# M710B.net
KiCad netlist of a schematic drawn in EAGLE
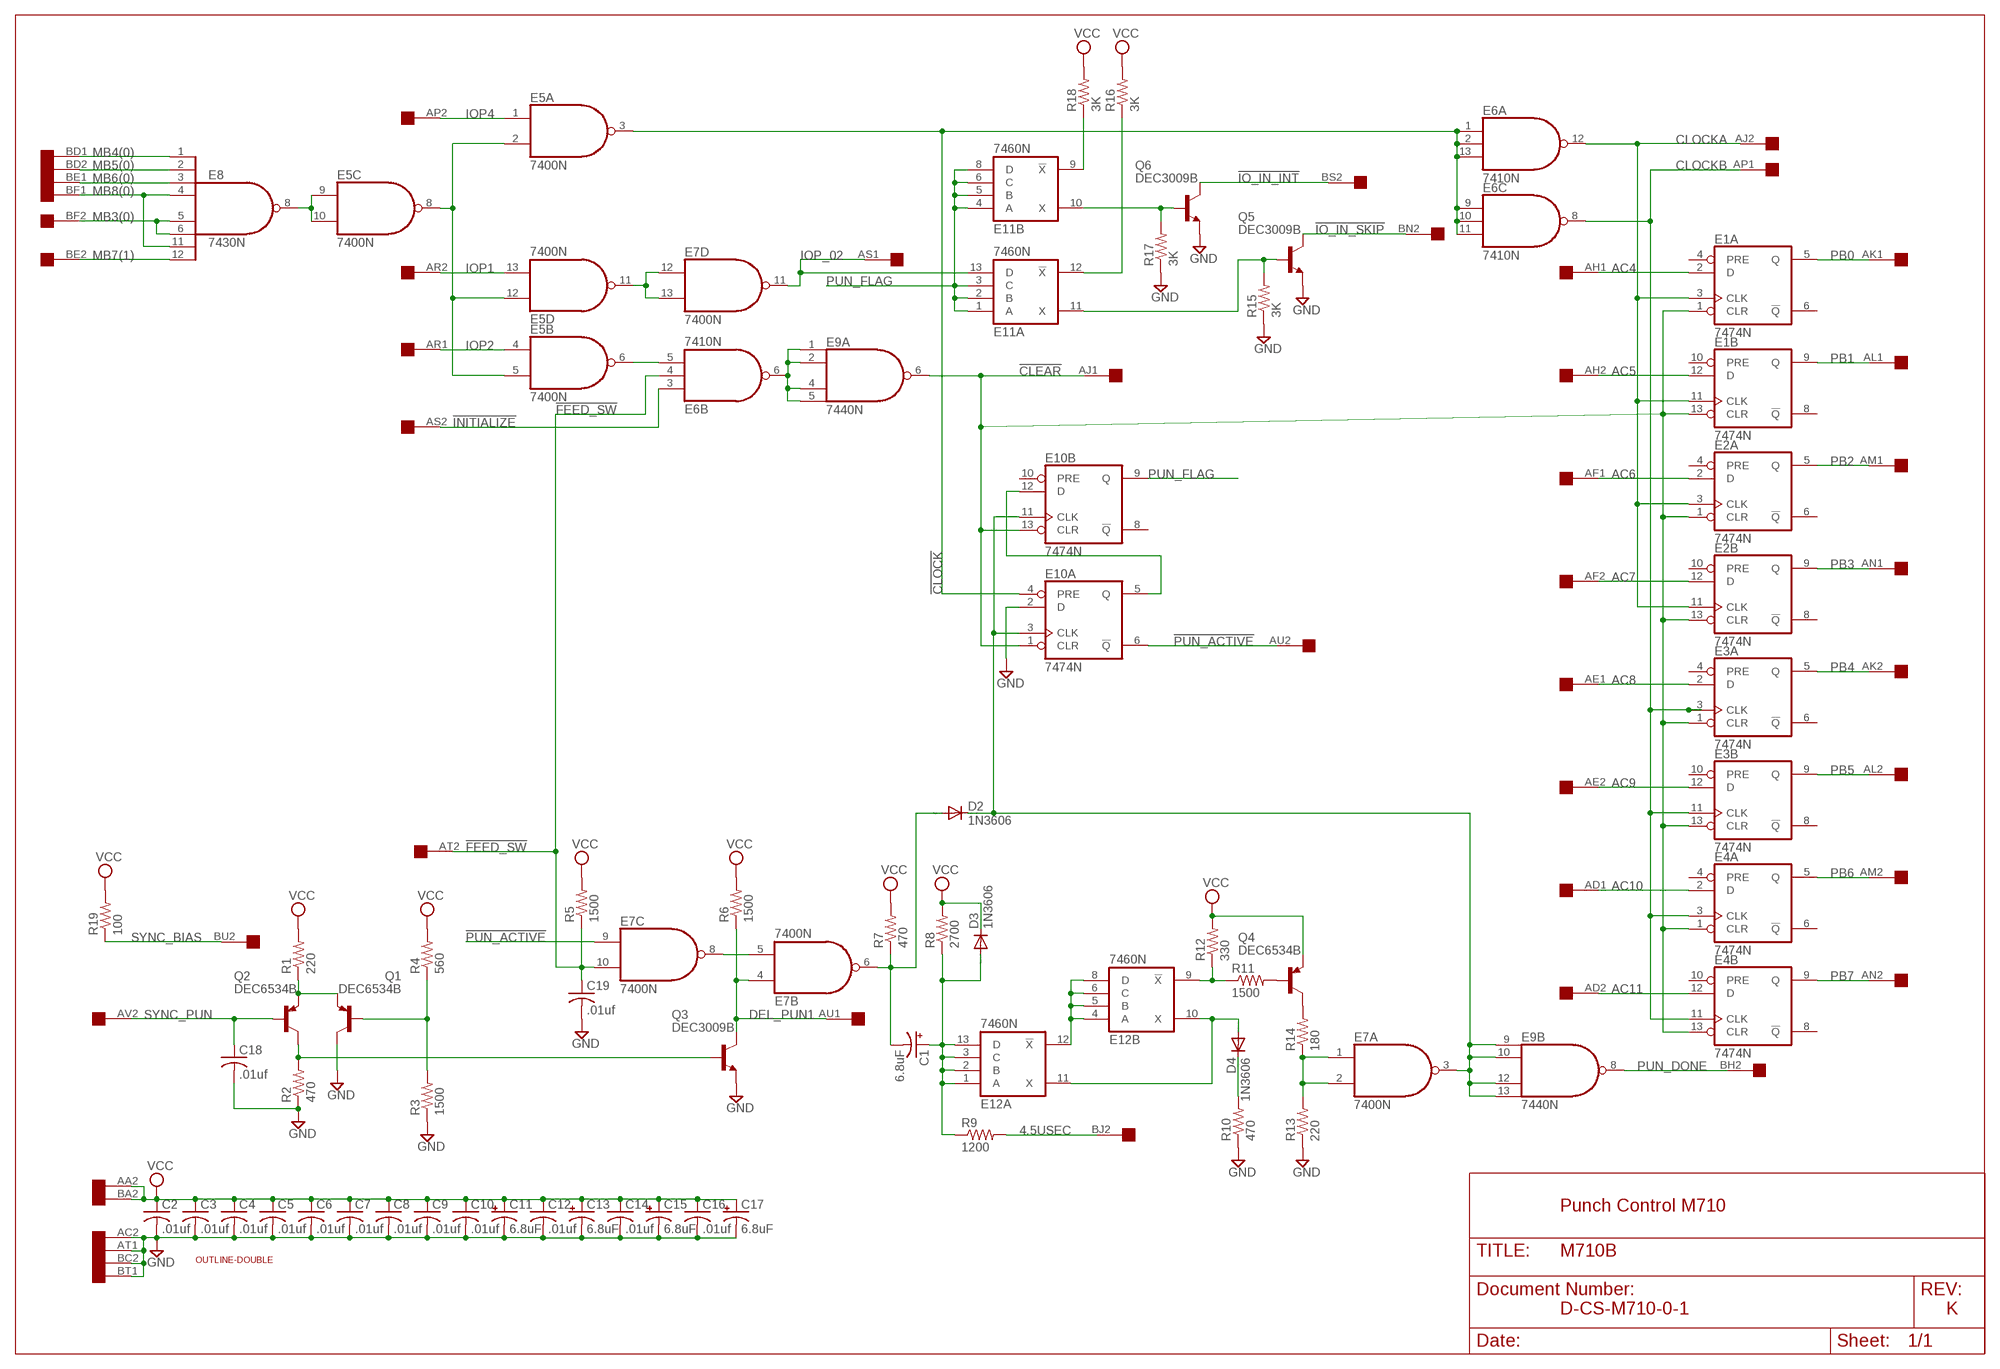
[diagram p0: schematic, sheet 1]

(export (version "E")
  (design (tool "Eeschema 10.0.6"))
  (components
    (comp (ref "C1")
      (value "6.8uF")
      (footprint "eagle-import:E15-5")
      (libsource (lib "eagle-import") (part "CPOL-USE15-5AXIAL"))
    )
    (comp (ref "C2")
      (value ".01uf")
      (footprint "eagle-import:C075-032X103")
      (libsource (lib "eagle-import") (part "C-US075-032X103"))
    )
    (comp (ref "C3")
      (value ".01uf")
      (footprint "eagle-import:C075-032X103")
      (libsource (lib "eagle-import") (part "C-US075-032X103"))
    )
    (comp (ref "C4")
      (value ".01uf")
      (footprint "eagle-import:C075-032X103")
      (libsource (lib "eagle-import") (part "C-US075-032X103"))
    )
    (comp (ref "C5")
      (value ".01uf")
      (footprint "eagle-import:C075-032X103")
      (libsource (lib "eagle-import") (part "C-US075-032X103"))
    )
    (comp (ref "C6")
      (value ".01uf")
      (footprint "eagle-import:C075-032X103")
      (libsource (lib "eagle-import") (part "C-US075-032X103"))
    )
    (comp (ref "C7")
      (value ".01uf")
      (footprint "eagle-import:C075-032X103")
      (libsource (lib "eagle-import") (part "C-US075-032X103"))
    )
    (comp (ref "C8")
      (value ".01uf")
      (footprint "eagle-import:C075-032X103")
      (libsource (lib "eagle-import") (part "C-US075-032X103"))
    )
    (comp (ref "C9")
      (value ".01uf")
      (footprint "eagle-import:C075-032X103")
      (libsource (lib "eagle-import") (part "C-US075-032X103"))
    )
    (comp (ref "C10")
      (value ".01uf")
      (footprint "eagle-import:C075-032X103")
      (libsource (lib "eagle-import") (part "C-US075-032X103"))
    )
    (comp (ref "C11")
      (value "6.8uF")
      (footprint "eagle-import:E15-5")
      (libsource (lib "eagle-import") (part "CPOL-USE15-5AXIAL"))
    )
    (comp (ref "C12")
      (value ".01uf")
      (footprint "eagle-import:C075-032X103")
      (libsource (lib "eagle-import") (part "C-US075-032X103"))
    )
    (comp (ref "C13")
      (value "6.8uF")
      (footprint "eagle-import:E15-5")
      (libsource (lib "eagle-import") (part "CPOL-USE15-5AXIAL"))
    )
    (comp (ref "C14")
      (value ".01uf")
      (footprint "eagle-import:C075-032X103")
      (libsource (lib "eagle-import") (part "C-US075-032X103"))
    )
    (comp (ref "C15")
      (value "6.8uF")
      (footprint "eagle-import:E15-5")
      (libsource (lib "eagle-import") (part "CPOL-USE15-5AXIAL"))
    )
    (comp (ref "C16")
      (value ".01uf")
      (footprint "eagle-import:C075-032X103")
      (libsource (lib "eagle-import") (part "C-US075-032X103"))
    )
    (comp (ref "C17")
      (value "6.8uF")
      (footprint "eagle-import:E15-5")
      (libsource (lib "eagle-import") (part "CPOL-USE15-5AXIAL"))
    )
    (comp (ref "C18")
      (value ".01uf")
      (footprint "eagle-import:C075-032X103")
      (libsource (lib "eagle-import") (part "C-US075-032X103"))
    )
    (comp (ref "C19")
      (value ".01uf")
      (footprint "eagle-import:C075-032X103")
      (libsource (lib "eagle-import") (part "C-US075-032X103"))
    )
    (comp (ref "D2")
      (value "1N3606")
      (footprint "eagle-import:SOD61B")
      (libsource (lib "eagle-import") (part "DIODE-SOD61B"))
    )
    (comp (ref "D3")
      (value "1N3606")
      (footprint "eagle-import:SOD61B")
      (libsource (lib "eagle-import") (part "DIODE-SOD61B"))
    )
    (comp (ref "D4")
      (value "1N3606")
      (footprint "eagle-import:SOD61B")
      (libsource (lib "eagle-import") (part "DIODE-SOD61B"))
    )
    (comp (ref "E1")
      (value "7474N")
      (footprint "eagle-import:DIL14")
      (libsource (lib "eagle-import") (part "7474NS"))
    )
    (comp (ref "E2")
      (value "7474N")
      (footprint "eagle-import:DIL14")
      (libsource (lib "eagle-import") (part "7474NS"))
    )
    (comp (ref "E3")
      (value "7474N")
      (footprint "eagle-import:DIL14")
      (libsource (lib "eagle-import") (part "7474NS"))
    )
    (comp (ref "E4")
      (value "7474N")
      (footprint "eagle-import:DIL14")
      (libsource (lib "eagle-import") (part "7474NS"))
    )
    (comp (ref "E5")
      (value "7400N")
      (footprint "eagle-import:DIL14")
      (libsource (lib "eagle-import") (part "7400N"))
    )
    (comp (ref "E6")
      (value "7410N")
      (footprint "eagle-import:DIL14")
      (libsource (lib "eagle-import") (part "7410N"))
    )
    (comp (ref "E7")
      (value "7400N")
      (footprint "eagle-import:DIL14")
      (libsource (lib "eagle-import") (part "7400N"))
    )
    (comp (ref "E8")
      (value "7430N")
      (footprint "eagle-import:DIL14")
      (libsource (lib "eagle-import") (part "7430N"))
    )
    (comp (ref "E9")
      (value "7440N")
      (footprint "eagle-import:DIL14")
      (libsource (lib "eagle-import") (part "7440N"))
    )
    (comp (ref "E10")
      (value "7474N")
      (footprint "eagle-import:DIL14")
      (libsource (lib "eagle-import") (part "7474NS"))
    )
    (comp (ref "E11")
      (value "7460N")
      (footprint "eagle-import:DIL14")
      (libsource (lib "eagle-import") (part "7460N"))
    )
    (comp (ref "E12")
      (value "7460N")
      (footprint "eagle-import:DIL14")
      (libsource (lib "eagle-import") (part "7460N"))
    )
    (comp (ref "Q1")
      (value "DEC6534B")
      (footprint "eagle-import:TO92-EBC")
      (libsource (lib "eagle-import") (part "-PNP-TO92-EBCBC327-16"))
    )
    (comp (ref "Q2")
      (value "DEC6534B")
      (footprint "eagle-import:TO92-EBC")
      (libsource (lib "eagle-import") (part "-PNP-TO92-EBCBC327-16"))
    )
    (comp (ref "Q3")
      (value "DEC3009B")
      (footprint "eagle-import:TO92-EBC")
      (libsource (lib "eagle-import") (part "-NPN-TO92-EBC92"))
    )
    (comp (ref "Q4")
      (value "DEC6534B")
      (footprint "eagle-import:TO92-EBC")
      (libsource (lib "eagle-import") (part "-PNP-TO92-EBCBC327-16"))
    )
    (comp (ref "Q5")
      (value "DEC3009B")
      (footprint "eagle-import:TO92-EBC")
      (libsource (lib "eagle-import") (part "-NPN-TO92-EBC92"))
    )
    (comp (ref "Q6")
      (value "DEC3009B")
      (footprint "eagle-import:TO92-EBC")
      (libsource (lib "eagle-import") (part "-NPN-TO92-EBC"))
    )
    (comp (ref "R1")
      (value "220")
      (footprint "eagle-import:0207_15")
      (libsource (lib "eagle-import") (part "R-US_0207/15"))
    )
    (comp (ref "R2")
      (value "470")
      (footprint "eagle-import:0207_15")
      (libsource (lib "eagle-import") (part "R-US_0207/15"))
    )
    (comp (ref "R3")
      (value "1500")
      (footprint "eagle-import:0207_15")
      (libsource (lib "eagle-import") (part "R-US_0207/15"))
    )
    (comp (ref "R4")
      (value "560")
      (footprint "eagle-import:0207_15")
      (libsource (lib "eagle-import") (part "R-US_0207/15"))
    )
    (comp (ref "R5")
      (value "1500")
      (footprint "eagle-import:0207_15")
      (libsource (lib "eagle-import") (part "R-US_0207/15"))
    )
    (comp (ref "R6")
      (value "1500")
      (footprint "eagle-import:0207_15")
      (libsource (lib "eagle-import") (part "R-US_0207/15"))
    )
    (comp (ref "R7")
      (value "470")
      (footprint "eagle-import:0207_15")
      (libsource (lib "eagle-import") (part "R-US_0207/15"))
    )
    (comp (ref "R8")
      (value "2700")
      (footprint "eagle-import:0207_15")
      (libsource (lib "eagle-import") (part "R-US_0207/15"))
    )
    (comp (ref "R9")
      (value "1200")
      (footprint "eagle-import:0207_15")
      (libsource (lib "eagle-import") (part "R-US_0207/15"))
    )
    (comp (ref "R10")
      (value "470")
      (footprint "eagle-import:0207_15")
      (libsource (lib "eagle-import") (part "R-US_0207/15"))
    )
    (comp (ref "R11")
      (value "1500")
      (footprint "eagle-import:0207_15")
      (libsource (lib "eagle-import") (part "R-US_0207/15"))
    )
    (comp (ref "R12")
      (value "330")
      (footprint "eagle-import:0207_15")
      (libsource (lib "eagle-import") (part "R-US_0207/15"))
    )
    (comp (ref "R13")
      (value "220")
      (footprint "eagle-import:0207_15")
      (libsource (lib "eagle-import") (part "R-US_0207/15"))
    )
    (comp (ref "R14")
      (value "180")
      (footprint "eagle-import:0207_15")
      (libsource (lib "eagle-import") (part "R-US_0207/15"))
    )
    (comp (ref "R15")
      (value "3K")
      (footprint "eagle-import:0207_15")
      (libsource (lib "eagle-import") (part "R-US_0207/15"))
    )
    (comp (ref "R16")
      (value "3K")
      (footprint "eagle-import:0207_15")
      (libsource (lib "eagle-import") (part "R-US_0207/15"))
    )
    (comp (ref "R17")
      (value "3K")
      (footprint "eagle-import:0207_15")
      (libsource (lib "eagle-import") (part "R-US_0207/15"))
    )
    (comp (ref "R18")
      (value "3K")
      (footprint "eagle-import:0207_15")
      (libsource (lib "eagle-import") (part "R-US_0207/15"))
    )
    (comp (ref "R19")
      (value "100")
      (footprint "eagle-import:0207_15")
      (libsource (lib "eagle-import") (part "R-US_0207/15"))
    )
    (comp (ref "U$1")
      (value "OUTLINE-DOUBLE")
      (footprint "eagle-import:DOUBLE")
      (libsource (lib "eagle-import") (part "OUTLINE-DOUBLE"))
    )
    (comp (ref "U$2")
      (value "DOUBLE")
      (footprint "eagle-import:EDGE-CON4")
      (libsource (lib "eagle-import") (part "DOUBLE"))
    )
  )
  (nets
    (net (code "1") (name "/4.5USEC") (class "Default")
      (node (ref "R9") (pin "2") (pinfunction "2_2") (pintype "passive"))
      (node (ref "U$2") (pin "BJ2") (pinfunction "1_BJ2") (pintype "bidirectional"))
    )
    (net (code "2") (name "/AC4") (class "Default")
      (node (ref "E1") (pin "2") (pinfunction "D_2") (pintype "input"))
      (node (ref "U$2") (pin "AH1") (pinfunction "1_AH1") (pintype "bidirectional"))
    )
    (net (code "3") (name "/AC5") (class "Default")
      (node (ref "E1") (pin "12") (pinfunction "D_12") (pintype "input"))
      (node (ref "U$2") (pin "AH2") (pinfunction "1_AH2") (pintype "bidirectional"))
    )
    (net (code "4") (name "/AC6") (class "Default")
      (node (ref "E2") (pin "2") (pinfunction "D_2") (pintype "input"))
      (node (ref "U$2") (pin "AF1") (pinfunction "1_AF1") (pintype "bidirectional"))
    )
    (net (code "5") (name "/AC7") (class "Default")
      (node (ref "E2") (pin "12") (pinfunction "D_12") (pintype "input"))
      (node (ref "U$2") (pin "AF2") (pinfunction "1_AF2") (pintype "bidirectional"))
    )
    (net (code "6") (name "/AC8") (class "Default")
      (node (ref "E3") (pin "2") (pinfunction "D_2") (pintype "input"))
      (node (ref "U$2") (pin "AE1") (pinfunction "1_AE1") (pintype "bidirectional"))
    )
    (net (code "7") (name "/AC9") (class "Default")
      (node (ref "E3") (pin "12") (pinfunction "D_12") (pintype "input"))
      (node (ref "U$2") (pin "AE2") (pinfunction "1_AE2") (pintype "bidirectional"))
    )
    (net (code "8") (name "/AC10") (class "Default")
      (node (ref "E4") (pin "2") (pinfunction "D_2") (pintype "input"))
      (node (ref "U$2") (pin "AD1") (pinfunction "1_AD1") (pintype "bidirectional"))
    )
    (net (code "9") (name "/AC11") (class "Default")
      (node (ref "E4") (pin "12") (pinfunction "D_12") (pintype "input"))
      (node (ref "U$2") (pin "AD2") (pinfunction "1_AD2") (pintype "bidirectional"))
    )
    (net (code "10") (name "/CLOCKA") (class "Default")
      (node (ref "E1") (pin "11") (pinfunction "CLK_11") (pintype "input"))
      (node (ref "E1") (pin "3") (pinfunction "CLK_3") (pintype "input"))
      (node (ref "E2") (pin "11") (pinfunction "CLK_11") (pintype "input"))
      (node (ref "E2") (pin "3") (pinfunction "CLK_3") (pintype "input"))
      (node (ref "E6") (pin "12") (pinfunction "O_12") (pintype "output"))
      (node (ref "U$2") (pin "AJ2") (pinfunction "1_AJ2") (pintype "bidirectional"))
    )
    (net (code "11") (name "/CLOCKB") (class "Default")
      (node (ref "E3") (pin "11") (pinfunction "CLK_11") (pintype "input"))
      (node (ref "E3") (pin "3") (pinfunction "CLK_3") (pintype "input"))
      (node (ref "E4") (pin "11") (pinfunction "CLK_11") (pintype "input"))
      (node (ref "E4") (pin "3") (pinfunction "CLK_3") (pintype "input"))
      (node (ref "E6") (pin "8") (pinfunction "O_8") (pintype "output"))
      (node (ref "U$2") (pin "AP1") (pinfunction "1_AP1") (pintype "bidirectional"))
    )
    (net (code "12") (name "/DEL_PUN1") (class "Default")
      (node (ref "E7") (pin "4") (pinfunction "I0_4") (pintype "input"))
      (node (ref "Q3") (pin "C") (pinfunction "C_C") (pintype "passive"))
      (node (ref "R6") (pin "1") (pinfunction "1_1") (pintype "passive"))
      (node (ref "U$2") (pin "AU1") (pinfunction "1_AU1") (pintype "bidirectional"))
    )
    (net (code "13") (name "/IOP1") (class "Default")
      (node (ref "E5") (pin "13") (pinfunction "I1_13") (pintype "input"))
      (node (ref "U$2") (pin "AR2") (pinfunction "1_AR2") (pintype "bidirectional"))
    )
    (net (code "14") (name "/IOP2") (class "Default")
      (node (ref "E5") (pin "4") (pinfunction "I0_4") (pintype "input"))
      (node (ref "U$2") (pin "AR1") (pinfunction "1_AR1") (pintype "bidirectional"))
    )
    (net (code "15") (name "/IOP4") (class "Default")
      (node (ref "E5") (pin "1") (pinfunction "I0_1") (pintype "input"))
      (node (ref "U$2") (pin "AP2") (pinfunction "1_AP2") (pintype "bidirectional"))
    )
    (net (code "16") (name "/IOP_02") (class "Default")
      (node (ref "E11") (pin "13") (pinfunction "D_13") (pintype "input"))
      (node (ref "E7") (pin "11") (pinfunction "O_11") (pintype "output"))
      (node (ref "U$2") (pin "AS1") (pinfunction "1_AS1") (pintype "bidirectional"))
    )
    (net (code "17") (name "/MB3(0)") (class "Default")
      (node (ref "E8") (pin "5") (pinfunction "I4_5") (pintype "input"))
      (node (ref "E8") (pin "6") (pinfunction "I5_6") (pintype "input"))
      (node (ref "U$2") (pin "BF2") (pinfunction "1_BF2") (pintype "bidirectional"))
    )
    (net (code "18") (name "/MB4(0)") (class "Default")
      (node (ref "E8") (pin "1") (pinfunction "I0_1") (pintype "input"))
      (node (ref "U$2") (pin "BD1") (pinfunction "1_BD1") (pintype "bidirectional"))
    )
    (net (code "19") (name "/MB5(0)") (class "Default")
      (node (ref "E8") (pin "2") (pinfunction "I1_2") (pintype "input"))
      (node (ref "U$2") (pin "BD2") (pinfunction "1_BD2") (pintype "bidirectional"))
    )
    (net (code "20") (name "/MB6(0)") (class "Default")
      (node (ref "E8") (pin "3") (pinfunction "I2_3") (pintype "input"))
      (node (ref "U$2") (pin "BE1") (pinfunction "1_BE1") (pintype "bidirectional"))
    )
    (net (code "21") (name "/MB7(1)") (class "Default")
      (node (ref "E8") (pin "12") (pinfunction "I7_12") (pintype "input"))
      (node (ref "U$2") (pin "BE2") (pinfunction "1_BE2") (pintype "bidirectional"))
    )
    (net (code "22") (name "/MB8(0)") (class "Default")
      (node (ref "E8") (pin "11") (pinfunction "I6_11") (pintype "input"))
      (node (ref "E8") (pin "4") (pinfunction "I3_4") (pintype "input"))
      (node (ref "U$2") (pin "BF1") (pinfunction "1_BF1") (pintype "bidirectional"))
    )
    (net (code "23") (name "/PB0") (class "Default")
      (node (ref "E1") (pin "5") (pinfunction "Q_5") (pintype "output"))
      (node (ref "U$2") (pin "AK1") (pinfunction "1_AK1") (pintype "bidirectional"))
    )
    (net (code "24") (name "/PB1") (class "Default")
      (node (ref "E1") (pin "9") (pinfunction "Q_9") (pintype "output"))
      (node (ref "U$2") (pin "AL1") (pinfunction "1_AL1") (pintype "bidirectional"))
    )
    (net (code "25") (name "/PB2") (class "Default")
      (node (ref "E2") (pin "5") (pinfunction "Q_5") (pintype "output"))
      (node (ref "U$2") (pin "AM1") (pinfunction "1_AM1") (pintype "bidirectional"))
    )
    (net (code "26") (name "/PB3") (class "Default")
      (node (ref "E2") (pin "9") (pinfunction "Q_9") (pintype "output"))
      (node (ref "U$2") (pin "AN1") (pinfunction "1_AN1") (pintype "bidirectional"))
    )
    (net (code "27") (name "/PB4") (class "Default")
      (node (ref "E3") (pin "5") (pinfunction "Q_5") (pintype "output"))
      (node (ref "U$2") (pin "AK2") (pinfunction "1_AK2") (pintype "bidirectional"))
    )
    (net (code "28") (name "/PB5") (class "Default")
      (node (ref "E3") (pin "9") (pinfunction "Q_9") (pintype "output"))
      (node (ref "U$2") (pin "AL2") (pinfunction "1_AL2") (pintype "bidirectional"))
    )
    (net (code "29") (name "/PB6") (class "Default")
      (node (ref "E4") (pin "5") (pinfunction "Q_5") (pintype "output"))
      (node (ref "U$2") (pin "AM2") (pinfunction "1_AM2") (pintype "bidirectional"))
    )
    (net (code "30") (name "/PB7") (class "Default")
      (node (ref "E4") (pin "9") (pinfunction "Q_9") (pintype "output"))
      (node (ref "U$2") (pin "AN2") (pinfunction "1_AN2") (pintype "bidirectional"))
    )
    (net (code "31") (name "/PUN_DONE") (class "Default")
      (node (ref "E9") (pin "8") (pinfunction "O_8") (pintype "output"))
      (node (ref "U$2") (pin "BH2") (pinfunction "1_BH2") (pintype "bidirectional"))
    )
    (net (code "32") (name "/PUN_FLAG") (class "Default")
      (node (ref "E10") (pin "9") (pinfunction "Q_9") (pintype "output"))
      (node (ref "E11") (pin "1") (pinfunction "A_1") (pintype "input"))
      (node (ref "E11") (pin "2") (pinfunction "B_2") (pintype "input"))
      (node (ref "E11") (pin "3") (pinfunction "C_3") (pintype "input"))
      (node (ref "E11") (pin "4") (pinfunction "A_4") (pintype "input"))
      (node (ref "E11") (pin "5") (pinfunction "B_5") (pintype "input"))
      (node (ref "E11") (pin "6") (pinfunction "C_6") (pintype "input"))
      (node (ref "E11") (pin "8") (pinfunction "D_8") (pintype "input"))
    )
    (net (code "33") (name "/SYNC_BIAS") (class "Default")
      (node (ref "R19") (pin "1") (pinfunction "1_1") (pintype "passive"))
      (node (ref "U$2") (pin "BU2") (pinfunction "1_BU2") (pintype "bidirectional"))
    )
    (net (code "34") (name "/SYNC_PUN") (class "Default")
      (node (ref "C18") (pin "1") (pinfunction "1_1") (pintype "passive"))
      (node (ref "Q2") (pin "B") (pinfunction "B_B") (pintype "passive"))
      (node (ref "U$2") (pin "AV2") (pinfunction "1_AV2") (pintype "bidirectional"))
    )
    (net (code "35") (name "/~{CLEAR}") (class "Default")
      (node (ref "E1") (pin "1") (pinfunction "CLR_1") (pintype "input"))
      (node (ref "E1") (pin "13") (pinfunction "CLR_13") (pintype "input"))
      (node (ref "E10") (pin "1") (pinfunction "CLR_1") (pintype "input"))
      (node (ref "E10") (pin "13") (pinfunction "CLR_13") (pintype "input"))
      (node (ref "E2") (pin "1") (pinfunction "CLR_1") (pintype "input"))
      (node (ref "E2") (pin "13") (pinfunction "CLR_13") (pintype "input"))
      (node (ref "E3") (pin "1") (pinfunction "CLR_1") (pintype "input"))
      (node (ref "E3") (pin "13") (pinfunction "CLR_13") (pintype "input"))
      (node (ref "E4") (pin "1") (pinfunction "CLR_1") (pintype "input"))
      (node (ref "E4") (pin "13") (pinfunction "CLR_13") (pintype "input"))
      (node (ref "E9") (pin "6") (pinfunction "O_6") (pintype "output"))
      (node (ref "U$2") (pin "AJ1") (pinfunction "1_AJ1") (pintype "bidirectional"))
    )
    (net (code "36") (name "/~{CLOCK}") (class "Default")
      (node (ref "E10") (pin "4") (pinfunction "PRE_4") (pintype "input"))
      (node (ref "E5") (pin "3") (pinfunction "O_3") (pintype "output"))
      (node (ref "E6") (pin "1") (pinfunction "I0_1") (pintype "input"))
      (node (ref "E6") (pin "10") (pinfunction "I1_10") (pintype "input"))
      (node (ref "E6") (pin "11") (pinfunction "I2_11") (pintype "input"))
      (node (ref "E6") (pin "13") (pinfunction "I2_13") (pintype "input"))
      (node (ref "E6") (pin "2") (pinfunction "I1_2") (pintype "input"))
      (node (ref "E6") (pin "9") (pinfunction "I0_9") (pintype "input"))
    )
    (net (code "37") (name "/~{FEED_SW}") (class "Default")
      (node (ref "C19") (pin "1") (pinfunction "1_1") (pintype "passive"))
      (node (ref "E6") (pin "4") (pinfunction "I1_4") (pintype "input"))
      (node (ref "E7") (pin "10") (pinfunction "I1_10") (pintype "input"))
      (node (ref "R5") (pin "1") (pinfunction "1_1") (pintype "passive"))
      (node (ref "U$2") (pin "AT2") (pinfunction "1_AT2") (pintype "bidirectional"))
    )
    (net (code "38") (name "/~{INITIALIZE}") (class "Default")
      (node (ref "E6") (pin "3") (pinfunction "I0_3") (pintype "input"))
      (node (ref "U$2") (pin "AS2") (pinfunction "1_AS2") (pintype "bidirectional"))
    )
    (net (code "39") (name "/~{IO_IN_INT}") (class "Default")
      (node (ref "Q6") (pin "C") (pinfunction "C_C") (pintype "passive"))
      (node (ref "U$2") (pin "BS2") (pinfunction "1_BS2") (pintype "bidirectional"))
    )
    (net (code "40") (name "/~{IO_IN_SKIP}") (class "Default")
      (node (ref "Q5") (pin "C") (pinfunction "C_C") (pintype "passive"))
      (node (ref "U$2") (pin "BN2") (pinfunction "1_BN2") (pintype "bidirectional"))
    )
    (net (code "41") (name "/~{PUN_ACTIVE}") (class "Default")
      (node (ref "E10") (pin "6") (pinfunction "~{Q}_6") (pintype "output"))
      (node (ref "E7") (pin "9") (pinfunction "I0_9") (pintype "input"))
      (node (ref "U$2") (pin "AU2") (pinfunction "1_AU2") (pintype "bidirectional"))
    )
    (net (code "42") (name "GND") (class "Default")
      (node (ref "C10") (pin "2") (pinfunction "2_2") (pintype "passive"))
      (node (ref "C11") (pin "-") (pinfunction "-_-") (pintype "passive"))
      (node (ref "C12") (pin "2") (pinfunction "2_2") (pintype "passive"))
      (node (ref "C13") (pin "-") (pinfunction "-_-") (pintype "passive"))
      (node (ref "C14") (pin "2") (pinfunction "2_2") (pintype "passive"))
      (node (ref "C15") (pin "-") (pinfunction "-_-") (pintype "passive"))
      (node (ref "C16") (pin "2") (pinfunction "2_2") (pintype "passive"))
      (node (ref "C17") (pin "-") (pinfunction "-_-") (pintype "passive"))
      (node (ref "C18") (pin "2") (pinfunction "2_2") (pintype "passive"))
      (node (ref "C19") (pin "2") (pinfunction "2_2") (pintype "passive"))
      (node (ref "C2") (pin "2") (pinfunction "2_2") (pintype "passive"))
      (node (ref "C3") (pin "2") (pinfunction "2_2") (pintype "passive"))
      (node (ref "C4") (pin "2") (pinfunction "2_2") (pintype "passive"))
      (node (ref "C5") (pin "2") (pinfunction "2_2") (pintype "passive"))
      (node (ref "C6") (pin "2") (pinfunction "2_2") (pintype "passive"))
      (node (ref "C7") (pin "2") (pinfunction "2_2") (pintype "passive"))
      (node (ref "C8") (pin "2") (pinfunction "2_2") (pintype "passive"))
      (node (ref "C9") (pin "2") (pinfunction "2_2") (pintype "passive"))
      (node (ref "E10") (pin "2") (pinfunction "D_2") (pintype "input"))
      (node (ref "Q1") (pin "C") (pinfunction "C_C") (pintype "passive"))
      (node (ref "Q3") (pin "E") (pinfunction "E_E") (pintype "passive"))
      (node (ref "Q5") (pin "E") (pinfunction "E_E") (pintype "passive"))
      (node (ref "Q6") (pin "E") (pinfunction "E_E") (pintype "passive"))
      (node (ref "R10") (pin "1") (pinfunction "1_1") (pintype "passive"))
      (node (ref "R13") (pin "1") (pinfunction "1_1") (pintype "passive"))
      (node (ref "R15") (pin "1") (pinfunction "1_1") (pintype "passive"))
      (node (ref "R17") (pin "1") (pinfunction "1_1") (pintype "passive"))
      (node (ref "R2") (pin "1") (pinfunction "1_1") (pintype "passive"))
      (node (ref "R3") (pin "1") (pinfunction "1_1") (pintype "passive"))
      (node (ref "U$2") (pin "AC2") (pinfunction "1_AC2") (pintype "bidirectional"))
      (node (ref "U$2") (pin "AT1") (pinfunction "1_AT1") (pintype "bidirectional"))
      (node (ref "U$2") (pin "BC2") (pinfunction "1_BC2") (pintype "bidirectional"))
      (node (ref "U$2") (pin "BT1") (pinfunction "1_BT1") (pintype "bidirectional"))
    )
    (net (code "43") (name "Net-(D4-PadC)") (class "Default")
      (node (ref "D4") (pin "C") (pinfunction "C_C") (pintype "passive"))
      (node (ref "R10") (pin "2") (pinfunction "2_2") (pintype "passive"))
    )
    (net (code "44") (name "Net-(E5A-I1)") (class "Default")
      (node (ref "E5") (pin "12") (pinfunction "I0_12") (pintype "input"))
      (node (ref "E5") (pin "2") (pinfunction "I1_2") (pintype "input"))
      (node (ref "E5") (pin "5") (pinfunction "I1_5") (pintype "input"))
      (node (ref "E5") (pin "8") (pinfunction "O_8") (pintype "output"))
    )
    (net (code "45") (name "Net-(E5B-O)") (class "Default")
      (node (ref "E5") (pin "6") (pinfunction "O_6") (pintype "output"))
      (node (ref "E6") (pin "5") (pinfunction "I2_5") (pintype "input"))
    )
    (net (code "46") (name "Net-(E5C-I0)") (class "Default")
      (node (ref "E5") (pin "10") (pinfunction "I1_10") (pintype "input"))
      (node (ref "E5") (pin "9") (pinfunction "I0_9") (pintype "input"))
      (node (ref "E8") (pin "8") (pinfunction "O_8") (pintype "output"))
    )
    (net (code "47") (name "Net-(E5D-O)") (class "Default")
      (node (ref "E5") (pin "11") (pinfunction "O_11") (pintype "output"))
      (node (ref "E7") (pin "12") (pinfunction "I0_12") (pintype "input"))
      (node (ref "E7") (pin "13") (pinfunction "I1_13") (pintype "input"))
    )
    (net (code "48") (name "Net-(E6B-O)") (class "Default")
      (node (ref "E6") (pin "6") (pinfunction "O_6") (pintype "output"))
      (node (ref "E9") (pin "1") (pinfunction "I0_1") (pintype "input"))
      (node (ref "E9") (pin "2") (pinfunction "I1_2") (pintype "input"))
      (node (ref "E9") (pin "4") (pinfunction "I2_4") (pintype "input"))
      (node (ref "E9") (pin "5") (pinfunction "I3_5") (pintype "input"))
    )
    (net (code "49") (name "Net-(E7A-I0)") (class "Default")
      (node (ref "E7") (pin "1") (pinfunction "I0_1") (pintype "input"))
      (node (ref "E7") (pin "2") (pinfunction "I1_2") (pintype "input"))
      (node (ref "R13") (pin "2") (pinfunction "2_2") (pintype "passive"))
      (node (ref "R14") (pin "1") (pinfunction "1_1") (pintype "passive"))
    )
    (net (code "50") (name "Net-(E7B-I1)") (class "Default")
      (node (ref "E7") (pin "5") (pinfunction "I1_5") (pintype "input"))
      (node (ref "E7") (pin "8") (pinfunction "O_8") (pintype "output"))
    )
    (net (code "51") (name "Net-(E7B-O)") (class "Default")
      (node (ref "C1") (pin "-") (pinfunction "-_-") (pintype "passive"))
      (node (ref "D2") (pin "A") (pinfunction "A_A") (pintype "passive"))
      (node (ref "E7") (pin "6") (pinfunction "O_6") (pintype "output"))
      (node (ref "R7") (pin "1") (pinfunction "1_1") (pintype "passive"))
    )
    (net (code "52") (name "Net-(E10A-CLK)") (class "Default")
      (node (ref "D2") (pin "C") (pinfunction "C_C") (pintype "passive"))
      (node (ref "E10") (pin "11") (pinfunction "CLK_11") (pintype "input"))
      (node (ref "E10") (pin "3") (pinfunction "CLK_3") (pintype "input"))
      (node (ref "E7") (pin "3") (pinfunction "O_3") (pintype "output"))
      (node (ref "E9") (pin "10") (pinfunction "I1_10") (pintype "input"))
      (node (ref "E9") (pin "12") (pinfunction "I2_12") (pintype "input"))
      (node (ref "E9") (pin "13") (pinfunction "I3_13") (pintype "input"))
      (node (ref "E9") (pin "9") (pinfunction "I0_9") (pintype "input"))
    )
    (net (code "53") (name "Net-(E10A-Q)") (class "Default")
      (node (ref "E10") (pin "12") (pinfunction "D_12") (pintype "input"))
      (node (ref "E10") (pin "5") (pinfunction "Q_5") (pintype "output"))
    )
    (net (code "54") (name "Net-(E11A-X)") (class "Default")
      (node (ref "E11") (pin "11") (pinfunction "X_11") (pintype "output"))
      (node (ref "Q5") (pin "B") (pinfunction "B_B") (pintype "passive"))
      (node (ref "R15") (pin "2") (pinfunction "2_2") (pintype "passive"))
    )
    (net (code "55") (name "Net-(E11A-~{X})") (class "Default")
      (node (ref "E11") (pin "12") (pinfunction "~{X}_12") (pintype "output"))
      (node (ref "R16") (pin "1") (pinfunction "1_1") (pintype "passive"))
    )
    (net (code "56") (name "Net-(E11B-X)") (class "Default")
      (node (ref "E11") (pin "10") (pinfunction "X_10") (pintype "output"))
      (node (ref "Q6") (pin "B") (pinfunction "B_B") (pintype "passive"))
      (node (ref "R17") (pin "2") (pinfunction "2_2") (pintype "passive"))
    )
    (net (code "57") (name "Net-(E11B-~{X})") (class "Default")
      (node (ref "E11") (pin "9") (pinfunction "~{X}_9") (pintype "output"))
      (node (ref "R18") (pin "1") (pinfunction "1_1") (pintype "passive"))
    )
    (net (code "58") (name "Net-(E12A-A)") (class "Default")
      (node (ref "C1") (pin "+") (pinfunction "+_+") (pintype "passive"))
      (node (ref "D3") (pin "A") (pinfunction "A_A") (pintype "passive"))
      (node (ref "E12") (pin "1") (pinfunction "A_1") (pintype "input"))
      (node (ref "E12") (pin "13") (pinfunction "D_13") (pintype "input"))
      (node (ref "E12") (pin "2") (pinfunction "B_2") (pintype "input"))
      (node (ref "E12") (pin "3") (pinfunction "C_3") (pintype "input"))
      (node (ref "R8") (pin "1") (pinfunction "1_1") (pintype "passive"))
      (node (ref "R9") (pin "1") (pinfunction "1_1") (pintype "passive"))
    )
    (net (code "59") (name "Net-(E12A-X)") (class "Default")
      (node (ref "D4") (pin "A") (pinfunction "A_A") (pintype "passive"))
      (node (ref "E12") (pin "10") (pinfunction "X_10") (pintype "output"))
      (node (ref "E12") (pin "11") (pinfunction "X_11") (pintype "output"))
    )
    (net (code "60") (name "Net-(E12A-~{X})") (class "Default")
      (node (ref "E12") (pin "12") (pinfunction "~{X}_12") (pintype "output"))
      (node (ref "E12") (pin "4") (pinfunction "A_4") (pintype "input"))
      (node (ref "E12") (pin "5") (pinfunction "B_5") (pintype "input"))
      (node (ref "E12") (pin "6") (pinfunction "C_6") (pintype "input"))
      (node (ref "E12") (pin "8") (pinfunction "D_8") (pintype "input"))
    )
    (net (code "61") (name "Net-(E12B-~{X})") (class "Default")
      (node (ref "E12") (pin "9") (pinfunction "~{X}_9") (pintype "output"))
      (node (ref "R11") (pin "1") (pinfunction "1_1") (pintype "passive"))
      (node (ref "R12") (pin "1") (pinfunction "1_1") (pintype "passive"))
    )
    (net (code "62") (name "Net-(Q1-PadB)") (class "Default")
      (node (ref "Q1") (pin "B") (pinfunction "B_B") (pintype "passive"))
      (node (ref "R3") (pin "2") (pinfunction "2_2") (pintype "passive"))
      (node (ref "R4") (pin "1") (pinfunction "1_1") (pintype "passive"))
    )
    (net (code "63") (name "Net-(Q1-PadE)") (class "Default")
      (node (ref "Q1") (pin "E") (pinfunction "E_E") (pintype "passive"))
      (node (ref "Q2") (pin "E") (pinfunction "E_E") (pintype "passive"))
      (node (ref "R1") (pin "1") (pinfunction "1_1") (pintype "passive"))
    )
    (net (code "64") (name "Net-(Q2-PadC)") (class "Default")
      (node (ref "Q2") (pin "C") (pinfunction "C_C") (pintype "passive"))
      (node (ref "Q3") (pin "B") (pinfunction "B_B") (pintype "passive"))
      (node (ref "R2") (pin "2") (pinfunction "2_2") (pintype "passive"))
    )
    (net (code "65") (name "Net-(Q4-PadB)") (class "Default")
      (node (ref "Q4") (pin "B") (pinfunction "B_B") (pintype "passive"))
      (node (ref "R11") (pin "2") (pinfunction "2_2") (pintype "passive"))
    )
    (net (code "66") (name "Net-(Q4-PadC)") (class "Default")
      (node (ref "Q4") (pin "C") (pinfunction "C_C") (pintype "passive"))
      (node (ref "R14") (pin "2") (pinfunction "2_2") (pintype "passive"))
    )
    (net (code "67") (name "VCC") (class "Default")
      (node (ref "C10") (pin "1") (pinfunction "1_1") (pintype "passive"))
      (node (ref "C11") (pin "+") (pinfunction "+_+") (pintype "passive"))
      (node (ref "C12") (pin "1") (pinfunction "1_1") (pintype "passive"))
      (node (ref "C13") (pin "+") (pinfunction "+_+") (pintype "passive"))
      (node (ref "C14") (pin "1") (pinfunction "1_1") (pintype "passive"))
      (node (ref "C15") (pin "+") (pinfunction "+_+") (pintype "passive"))
      (node (ref "C16") (pin "1") (pinfunction "1_1") (pintype "passive"))
      (node (ref "C17") (pin "+") (pinfunction "+_+") (pintype "passive"))
      (node (ref "C2") (pin "1") (pinfunction "1_1") (pintype "passive"))
      (node (ref "C3") (pin "1") (pinfunction "1_1") (pintype "passive"))
      (node (ref "C4") (pin "1") (pinfunction "1_1") (pintype "passive"))
      (node (ref "C5") (pin "1") (pinfunction "1_1") (pintype "passive"))
      (node (ref "C6") (pin "1") (pinfunction "1_1") (pintype "passive"))
      (node (ref "C7") (pin "1") (pinfunction "1_1") (pintype "passive"))
      (node (ref "C8") (pin "1") (pinfunction "1_1") (pintype "passive"))
      (node (ref "C9") (pin "1") (pinfunction "1_1") (pintype "passive"))
      (node (ref "D3") (pin "C") (pinfunction "C_C") (pintype "passive"))
      (node (ref "Q4") (pin "E") (pinfunction "E_E") (pintype "passive"))
      (node (ref "R1") (pin "2") (pinfunction "2_2") (pintype "passive"))
      (node (ref "R12") (pin "2") (pinfunction "2_2") (pintype "passive"))
      (node (ref "R16") (pin "2") (pinfunction "2_2") (pintype "passive"))
      (node (ref "R18") (pin "2") (pinfunction "2_2") (pintype "passive"))
      (node (ref "R19") (pin "2") (pinfunction "2_2") (pintype "passive"))
      (node (ref "R4") (pin "2") (pinfunction "2_2") (pintype "passive"))
      (node (ref "R5") (pin "2") (pinfunction "2_2") (pintype "passive"))
      (node (ref "R6") (pin "2") (pinfunction "2_2") (pintype "passive"))
      (node (ref "R7") (pin "2") (pinfunction "2_2") (pintype "passive"))
      (node (ref "R8") (pin "2") (pinfunction "2_2") (pintype "passive"))
      (node (ref "U$2") (pin "AA2") (pinfunction "1_AA2") (pintype "bidirectional"))
      (node (ref "U$2") (pin "BA2") (pinfunction "1_BA2") (pintype "bidirectional"))
    )
    (net (code "68") (name "unconnected-(E1A-PRE-Pad4)") (class "Default")
      (node (ref "E1") (pin "4") (pinfunction "PRE_4") (pintype "input"))
    )
    (net (code "69") (name "unconnected-(E1A-~{Q}-Pad6)") (class "Default")
      (node (ref "E1") (pin "6") (pinfunction "~{Q}_6") (pintype "output"))
    )
    (net (code "70") (name "unconnected-(E1B-PRE-Pad10)") (class "Default")
      (node (ref "E1") (pin "10") (pinfunction "PRE_10") (pintype "input"))
    )
    (net (code "71") (name "unconnected-(E1B-~{Q}-Pad8)") (class "Default")
      (node (ref "E1") (pin "8") (pinfunction "~{Q}_8") (pintype "output"))
    )
    (net (code "72") (name "unconnected-(E2A-PRE-Pad4)") (class "Default")
      (node (ref "E2") (pin "4") (pinfunction "PRE_4") (pintype "input"))
    )
    (net (code "73") (name "unconnected-(E2A-~{Q}-Pad6)") (class "Default")
      (node (ref "E2") (pin "6") (pinfunction "~{Q}_6") (pintype "output"))
    )
    (net (code "74") (name "unconnected-(E2B-PRE-Pad10)") (class "Default")
      (node (ref "E2") (pin "10") (pinfunction "PRE_10") (pintype "input"))
    )
    (net (code "75") (name "unconnected-(E2B-~{Q}-Pad8)") (class "Default")
      (node (ref "E2") (pin "8") (pinfunction "~{Q}_8") (pintype "output"))
    )
    (net (code "76") (name "unconnected-(E3A-PRE-Pad4)") (class "Default")
      (node (ref "E3") (pin "4") (pinfunction "PRE_4") (pintype "input"))
    )
    (net (code "77") (name "unconnected-(E3A-~{Q}-Pad6)") (class "Default")
      (node (ref "E3") (pin "6") (pinfunction "~{Q}_6") (pintype "output"))
    )
    (net (code "78") (name "unconnected-(E3B-PRE-Pad10)") (class "Default")
      (node (ref "E3") (pin "10") (pinfunction "PRE_10") (pintype "input"))
    )
    (net (code "79") (name "unconnected-(E3B-~{Q}-Pad8)") (class "Default")
      (node (ref "E3") (pin "8") (pinfunction "~{Q}_8") (pintype "output"))
    )
    (net (code "80") (name "unconnected-(E4A-PRE-Pad4)") (class "Default")
      (node (ref "E4") (pin "4") (pinfunction "PRE_4") (pintype "input"))
    )
    (net (code "81") (name "unconnected-(E4A-~{Q}-Pad6)") (class "Default")
      (node (ref "E4") (pin "6") (pinfunction "~{Q}_6") (pintype "output"))
    )
    (net (code "82") (name "unconnected-(E4B-PRE-Pad10)") (class "Default")
      (node (ref "E4") (pin "10") (pinfunction "PRE_10") (pintype "input"))
    )
    (net (code "83") (name "unconnected-(E4B-~{Q}-Pad8)") (class "Default")
      (node (ref "E4") (pin "8") (pinfunction "~{Q}_8") (pintype "output"))
    )
    (net (code "84") (name "unconnected-(E10B-PRE-Pad10)") (class "Default")
      (node (ref "E10") (pin "10") (pinfunction "PRE_10") (pintype "input"))
    )
    (net (code "85") (name "unconnected-(E10B-~{Q}-Pad8)") (class "Default")
      (node (ref "E10") (pin "8") (pinfunction "~{Q}_8") (pintype "output"))
    )
  )
)
